# ZX_Loader.net
KiCad netlist of a schematic drawn in EAGLE
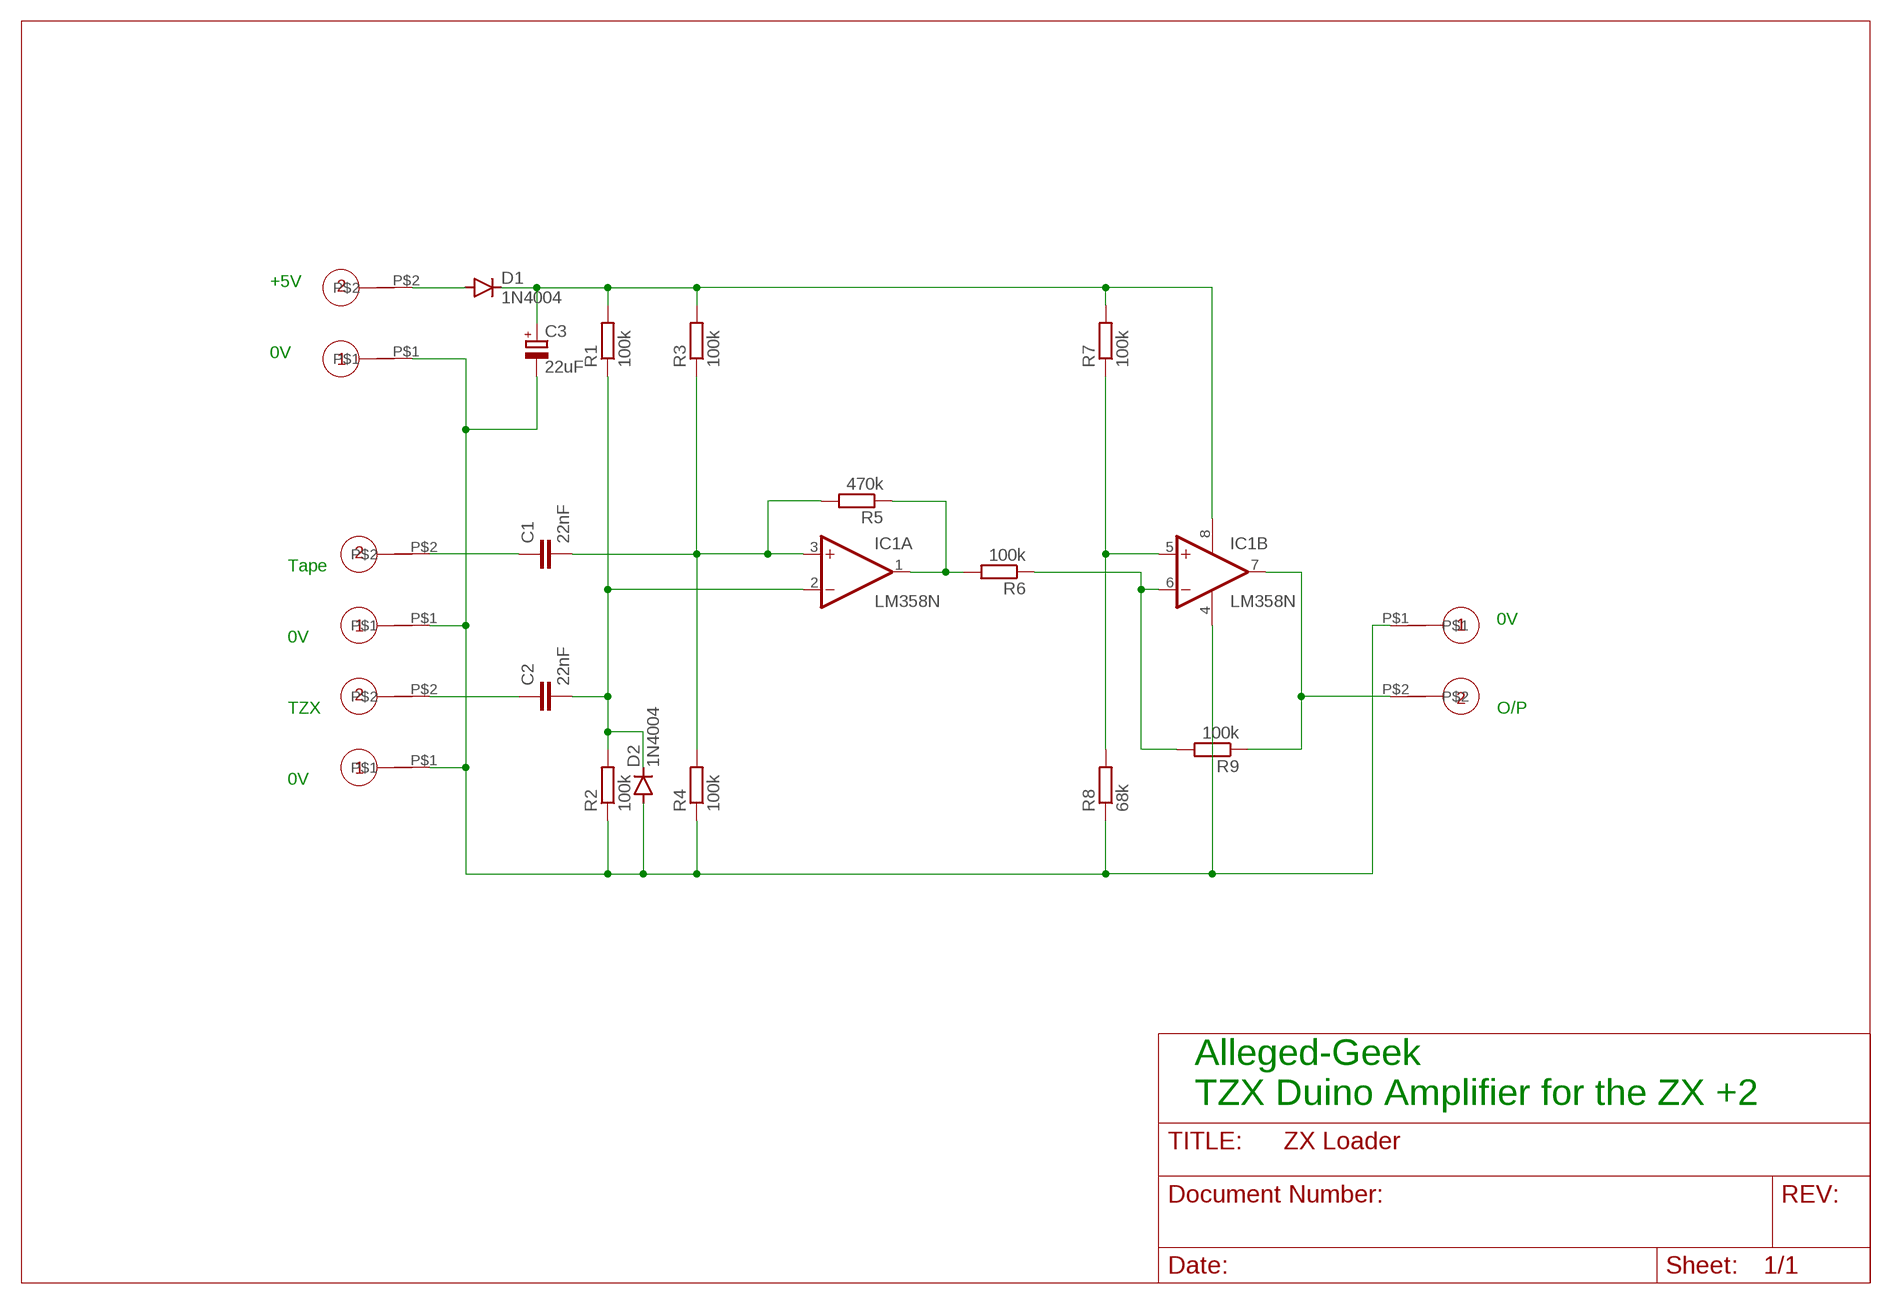
[diagram p0: schematic, sheet 1]

(export (version "E")
  (design (tool "Eeschema 10.0.6"))
  (components
    (comp (ref "C1")
      (value "22nF")
      (footprint "eagle-import:C050-030X075")
      (libsource (lib "eagle-import") (part "C-EU050-030X075"))
    )
    (comp (ref "C2")
      (value "22nF")
      (footprint "eagle-import:C050-030X075")
      (libsource (lib "eagle-import") (part "C-EU050-030X075"))
    )
    (comp (ref "C3")
      (value "22uF")
      (footprint "eagle-import:E2,5-5")
      (libsource (lib "eagle-import") (part "CPOL-EUE2.5-5"))
    )
    (comp (ref "D1")
      (value "1N4004")
      (footprint "eagle-import:DO41-10")
      (libsource (lib "eagle-import") (part "1N4004"))
    )
    (comp (ref "D2")
      (value "1N4004")
      (footprint "eagle-import:DO41-10")
      (libsource (lib "eagle-import") (part "1N4004"))
    )
    (comp (ref "IC1")
      (value "LM358N")
      (footprint "eagle-import:DIL08")
      (libsource (lib "eagle-import") (part "LM358N"))
    )
    (comp (ref "O/P")
      (value "RGU-A2-PUSH-BUTTON-CONNECTOR")
      (footprint "eagle-import:RGU-A2")
      (fields (field (name "MF") "Rapid") (field (name "MPN") "21-2626"))
      (libsource (lib "eagle-import") (part "RGU-A2-PUSH-BUTTON-CONNECTOR"))
    )
    (comp (ref "POWER")
      (value "Power")
      (footprint "eagle-import:RGU-A2")
      (fields (field (name "MF") "Rapid") (field (name "MPN") "21-2626"))
      (libsource (lib "eagle-import") (part "RGU-A2-PUSH-BUTTON-CONNECTOR"))
    )
    (comp (ref "R1")
      (value "100k")
      (footprint "eagle-import:0207_10")
      (libsource (lib "eagle-import") (part "RGU-RESISTOR-207/10"))
    )
    (comp (ref "R2")
      (value "100k")
      (footprint "eagle-import:0207_10")
      (libsource (lib "eagle-import") (part "RGU-RESISTOR-207/10"))
    )
    (comp (ref "R3")
      (value "100k")
      (footprint "eagle-import:0207_10")
      (libsource (lib "eagle-import") (part "RGU-RESISTOR-207/10"))
    )
    (comp (ref "R4")
      (value "100k")
      (footprint "eagle-import:0207_10")
      (libsource (lib "eagle-import") (part "RGU-RESISTOR-207/10"))
    )
    (comp (ref "R5")
      (value "470k")
      (footprint "eagle-import:0207_10")
      (libsource (lib "eagle-import") (part "RGU-RESISTOR-207/10"))
    )
    (comp (ref "R6")
      (value "100k")
      (footprint "eagle-import:0207_10")
      (libsource (lib "eagle-import") (part "RGU-RESISTOR-207/10"))
    )
    (comp (ref "R7")
      (value "100k")
      (footprint "eagle-import:0207_10")
      (libsource (lib "eagle-import") (part "RGU-RESISTOR-207/10"))
    )
    (comp (ref "R8")
      (value "68k")
      (footprint "eagle-import:0207_10")
      (libsource (lib "eagle-import") (part "RGU-RESISTOR-207/10"))
    )
    (comp (ref "R9")
      (value "100k")
      (footprint "eagle-import:0207_10")
      (libsource (lib "eagle-import") (part "RGU-RESISTOR-207/10"))
    )
    (comp (ref "TZX")
      (value "RGU-A2-PUSH-BUTTON-CONNECTOR")
      (footprint "eagle-import:RGU-A2")
      (fields (field (name "MF") "Rapid") (field (name "MPN") "21-2626"))
      (libsource (lib "eagle-import") (part "RGU-A2-PUSH-BUTTON-CONNECTOR"))
    )
    (comp (ref "U2")
      (value "Tape")
      (footprint "eagle-import:RGU-A2")
      (fields (field (name "MF") "Rapid") (field (name "MPN") "21-2626"))
      (libsource (lib "eagle-import") (part "RGU-A2-PUSH-BUTTON-CONNECTOR"))
    )
  )
  (nets
    (net (code "1") (name "Net-(C1-Pad1)") (class "Default")
      (node (ref "C1") (pin "1") (pinfunction "1_1") (pintype "passive"))
      (node (ref "U2") (pin "P$2") (pinfunction "P$2_P$2") (pintype "bidirectional"))
    )
    (net (code "2") (name "Net-(C2-Pad1)") (class "Default")
      (node (ref "C2") (pin "1") (pinfunction "1_1") (pintype "passive"))
      (node (ref "TZX") (pin "P$2") (pinfunction "P$2_P$2") (pintype "bidirectional"))
    )
    (net (code "3") (name "Net-(D1-PadA)") (class "Default")
      (node (ref "D1") (pin "A") (pinfunction "A_A") (pintype "passive"))
      (node (ref "POWER") (pin "P$2") (pinfunction "P$2_P$2") (pintype "bidirectional"))
    )
    (net (code "4") (name "Net-(IC1A-+IN)") (class "Default")
      (node (ref "C1") (pin "2") (pinfunction "2_2") (pintype "passive"))
      (node (ref "IC1") (pin "3") (pinfunction "+IN_3") (pintype "input"))
      (node (ref "R3") (pin "1") (pinfunction "1_1") (pintype "passive"))
      (node (ref "R4") (pin "2") (pinfunction "2_2") (pintype "passive"))
      (node (ref "R5") (pin "2") (pinfunction "2_2") (pintype "passive"))
    )
    (net (code "5") (name "Net-(IC1A--IN)") (class "Default")
      (node (ref "C2") (pin "2") (pinfunction "2_2") (pintype "passive"))
      (node (ref "D2") (pin "C") (pinfunction "C_C") (pintype "passive"))
      (node (ref "IC1") (pin "2") (pinfunction "-IN_2") (pintype "input"))
      (node (ref "R1") (pin "1") (pinfunction "1_1") (pintype "passive"))
      (node (ref "R2") (pin "2") (pinfunction "2_2") (pintype "passive"))
    )
    (net (code "6") (name "Net-(IC1A-OUT)") (class "Default")
      (node (ref "IC1") (pin "1") (pinfunction "OUT_1") (pintype "output"))
      (node (ref "R5") (pin "1") (pinfunction "1_1") (pintype "passive"))
      (node (ref "R6") (pin "2") (pinfunction "2_2") (pintype "passive"))
    )
    (net (code "7") (name "Net-(IC1B-+IN)") (class "Default")
      (node (ref "IC1") (pin "5") (pinfunction "+IN_5") (pintype "input"))
      (node (ref "R7") (pin "1") (pinfunction "1_1") (pintype "passive"))
      (node (ref "R8") (pin "2") (pinfunction "2_2") (pintype "passive"))
    )
    (net (code "8") (name "Net-(IC1B--IN)") (class "Default")
      (node (ref "IC1") (pin "6") (pinfunction "-IN_6") (pintype "input"))
      (node (ref "R6") (pin "1") (pinfunction "1_1") (pintype "passive"))
      (node (ref "R9") (pin "2") (pinfunction "2_2") (pintype "passive"))
    )
    (net (code "9") (name "Net-(IC1B-OUT)") (class "Default")
      (node (ref "IC1") (pin "7") (pinfunction "OUT_7") (pintype "output"))
      (node (ref "O/P") (pin "P$2") (pinfunction "P$2_P$2") (pintype "bidirectional"))
      (node (ref "R9") (pin "1") (pinfunction "1_1") (pintype "passive"))
    )
    (net (code "10") (name "Net-(IC1C-V+)") (class "Default")
      (node (ref "C3") (pin "+") (pinfunction "+_+") (pintype "passive"))
      (node (ref "D1") (pin "C") (pinfunction "C_C") (pintype "passive"))
      (node (ref "IC1") (pin "8") (pinfunction "V+_8") (pintype "power_in"))
      (node (ref "R1") (pin "2") (pinfunction "2_2") (pintype "passive"))
      (node (ref "R3") (pin "2") (pinfunction "2_2") (pintype "passive"))
      (node (ref "R7") (pin "2") (pinfunction "2_2") (pintype "passive"))
    )
    (net (code "11") (name "Net-(IC1C-V-)") (class "Default")
      (node (ref "C3") (pin "-") (pinfunction "-_-") (pintype "passive"))
      (node (ref "D2") (pin "A") (pinfunction "A_A") (pintype "passive"))
      (node (ref "IC1") (pin "4") (pinfunction "V-_4") (pintype "power_in"))
      (node (ref "O/P") (pin "P$1") (pinfunction "P$1_P$1") (pintype "bidirectional"))
      (node (ref "POWER") (pin "P$1") (pinfunction "P$1_P$1") (pintype "bidirectional"))
      (node (ref "R2") (pin "1") (pinfunction "1_1") (pintype "passive"))
      (node (ref "R4") (pin "1") (pinfunction "1_1") (pintype "passive"))
      (node (ref "R8") (pin "1") (pinfunction "1_1") (pintype "passive"))
      (node (ref "TZX") (pin "P$1") (pinfunction "P$1_P$1") (pintype "bidirectional"))
      (node (ref "U2") (pin "P$1") (pinfunction "P$1_P$1") (pintype "bidirectional"))
    )
  )
)
